# litebrite2_3.net
KiCad netlist of a schematic drawn in EAGLE
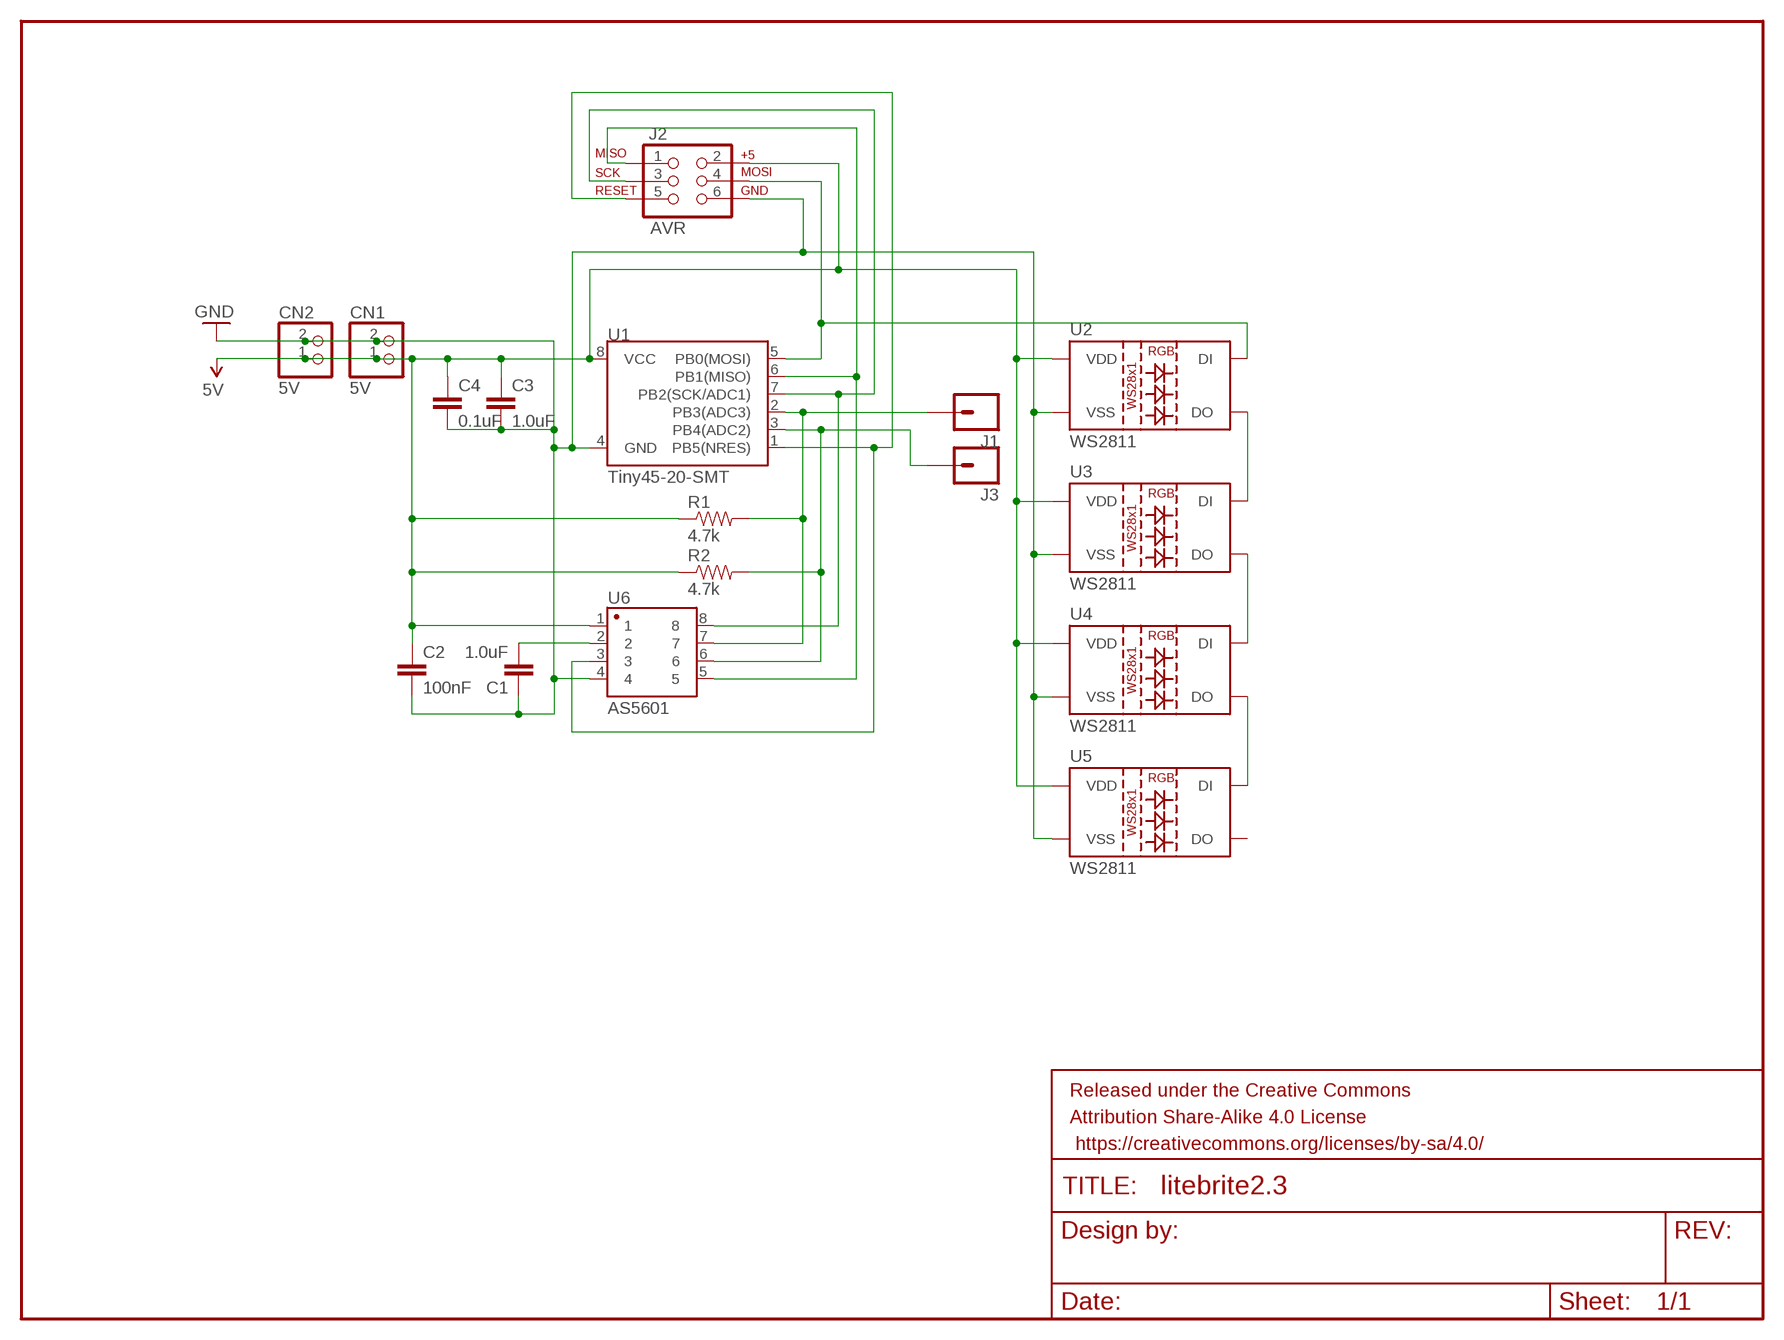
[diagram p0: schematic, sheet 1]

(export (version "E")
  (design (tool "Eeschema 10.0.6"))
  (components
    (comp (ref "C1")
      (value "1.0uF")
      (footprint "eagle-import:0402-CAP")
      (libsource (lib "eagle-import") (part "1.0UF-16V-10%(0402)"))
    )
    (comp (ref "C2")
      (value "100nF")
      (footprint "eagle-import:0402-CAP")
      (libsource (lib "eagle-import") (part "CAP0402-CAP"))
    )
    (comp (ref "C3")
      (value "1.0uF")
      (footprint "eagle-import:0402-CAP")
      (libsource (lib "eagle-import") (part "1.0UF-16V-10%(0402)"))
    )
    (comp (ref "C4")
      (value "0.1uF")
      (footprint "eagle-import:0402-CAP")
      (libsource (lib "eagle-import") (part "0.1UF-16V(+-10%)(0402)"))
    )
    (comp (ref "CN1")
      (value "5V")
      (footprint "eagle-import:JST-PH-2-SMT-RA")
      (libsource (lib "eagle-import") (part "JST_2PIN-SMT-RA"))
    )
    (comp (ref "CN2")
      (value "5V")
      (footprint "eagle-import:JST-PH-2-SMT-RA")
      (libsource (lib "eagle-import") (part "JST_2PIN-SMT-RA"))
    )
    (comp (ref "FRAME1")
      (value "FRAME-LETTERNO_PACKAGE")
      (footprint "eagle-import:DUMMY")
      (fields (field (name "DESIGNER") "Nobody"))
      (libsource (lib "eagle-import") (part "FRAME-LETTERNO_PACKAGE"))
    )
    (comp (ref "J1")
      (value "M01SMD")
      (footprint "eagle-import:LUXEON-PAD")
      (libsource (lib "eagle-import") (part "M01SMD"))
    )
    (comp (ref "J2")
      (value "AVR")
      (footprint "eagle-import:2X3")
      (libsource (lib "eagle-import") (part "AVR_SPI_PRG_6PTH"))
    )
    (comp (ref "J3")
      (value "M01SMD")
      (footprint "eagle-import:LUXEON-PAD")
      (libsource (lib "eagle-import") (part "M01SMD"))
    )
    (comp (ref "R1")
      (value "4.7k")
      (footprint "eagle-import:0603-RES")
      (libsource (lib "eagle-import") (part "4.7OHM-1/10W-5%(0603)"))
    )
    (comp (ref "R2")
      (value "4.7k")
      (footprint "eagle-import:0603-RES")
      (libsource (lib "eagle-import") (part "4.7OHM-1/10W-5%(0603)"))
    )
    (comp (ref "U1")
      (value "Tiny45-20-SMT")
      (footprint "eagle-import:SO08-EIAJ")
      (libsource (lib "eagle-import") (part "ATTINY45TINY45-20-SMT"))
    )
    (comp (ref "U2")
      (value "WS2811")
      (footprint "eagle-import:LED-TRICOLOR-5050-IC")
      (libsource (lib "eagle-import") (part "LED-TRICOLOR-5050-ICWS2811"))
    )
    (comp (ref "U3")
      (value "WS2811")
      (footprint "eagle-import:LED-TRICOLOR-5050-IC")
      (libsource (lib "eagle-import") (part "LED-TRICOLOR-5050-ICWS2811"))
    )
    (comp (ref "U4")
      (value "WS2811")
      (footprint "eagle-import:LED-TRICOLOR-5050-IC")
      (libsource (lib "eagle-import") (part "LED-TRICOLOR-5050-ICWS2811"))
    )
    (comp (ref "U5")
      (value "WS2811")
      (footprint "eagle-import:LED-TRICOLOR-5050-IC")
      (libsource (lib "eagle-import") (part "LED-TRICOLOR-5050-ICWS2811"))
    )
    (comp (ref "U6")
      (value "AS5601")
      (footprint "eagle-import:SO08")
      (libsource (lib "eagle-import") (part "GENERIC-SOIC8MSGEQ7N-FILTER"))
    )
  )
  (nets
    (net (code "1") (name "5V") (class "Default")
      (node (ref "C2") (pin "1") (pinfunction "1_1") (pintype "passive"))
      (node (ref "C3") (pin "1") (pinfunction "1_1") (pintype "passive"))
      (node (ref "C4") (pin "1") (pinfunction "1_1") (pintype "passive"))
      (node (ref "CN1") (pin "1") (pinfunction "2_1") (pintype "passive"))
      (node (ref "CN2") (pin "1") (pinfunction "2_1") (pintype "passive"))
      (node (ref "J2") (pin "2") (pinfunction "2_2") (pintype "passive"))
      (node (ref "R1") (pin "1") (pinfunction "1_1") (pintype "passive"))
      (node (ref "R2") (pin "1") (pinfunction "1_1") (pintype "passive"))
      (node (ref "U1") (pin "8") (pinfunction "VCC_8") (pintype "bidirectional"))
      (node (ref "U2") (pin "3") (pinfunction "VDD_3") (pintype "bidirectional"))
      (node (ref "U2") (pin "5") (pinfunction "VDD_5") (pintype "bidirectional"))
      (node (ref "U3") (pin "3") (pinfunction "VDD_3") (pintype "bidirectional"))
      (node (ref "U3") (pin "5") (pinfunction "VDD_5") (pintype "bidirectional"))
      (node (ref "U4") (pin "3") (pinfunction "VDD_3") (pintype "bidirectional"))
      (node (ref "U4") (pin "5") (pinfunction "VDD_5") (pintype "bidirectional"))
      (node (ref "U5") (pin "3") (pinfunction "VDD_3") (pintype "bidirectional"))
      (node (ref "U5") (pin "5") (pinfunction "VDD_5") (pintype "bidirectional"))
      (node (ref "U6") (pin "1") (pinfunction "1_1") (pintype "bidirectional"))
    )
    (net (code "2") (name "GND") (class "Default")
      (node (ref "C1") (pin "1") (pinfunction "1_1") (pintype "passive"))
      (node (ref "C2") (pin "2") (pinfunction "2_2") (pintype "passive"))
      (node (ref "C3") (pin "2") (pinfunction "2_2") (pintype "passive"))
      (node (ref "C4") (pin "2") (pinfunction "2_2") (pintype "passive"))
      (node (ref "CN1") (pin "2") (pinfunction "1_2") (pintype "passive"))
      (node (ref "CN2") (pin "2") (pinfunction "1_2") (pintype "passive"))
      (node (ref "J2") (pin "6") (pinfunction "6_6") (pintype "passive"))
      (node (ref "U1") (pin "4") (pinfunction "GND_4") (pintype "bidirectional"))
      (node (ref "U2") (pin "6") (pinfunction "VSS_6") (pintype "bidirectional"))
      (node (ref "U3") (pin "6") (pinfunction "VSS_6") (pintype "bidirectional"))
      (node (ref "U4") (pin "6") (pinfunction "VSS_6") (pintype "bidirectional"))
      (node (ref "U5") (pin "6") (pinfunction "VSS_6") (pintype "bidirectional"))
      (node (ref "U6") (pin "4") (pinfunction "4_4") (pintype "bidirectional"))
    )
    (net (code "3") (name "Net-(C1-Pad2)") (class "Default")
      (node (ref "C1") (pin "2") (pinfunction "2_2") (pintype "passive"))
      (node (ref "U6") (pin "2") (pinfunction "2_2") (pintype "bidirectional"))
    )
    (net (code "4") (name "Net-(J1-1)") (class "Default")
      (node (ref "J1") (pin "P$1") (pinfunction "1_P$1") (pintype "passive"))
      (node (ref "R1") (pin "2") (pinfunction "2_2") (pintype "passive"))
      (node (ref "U1") (pin "2") (pinfunction "PB3(ADC3)_2") (pintype "bidirectional"))
      (node (ref "U6") (pin "7") (pinfunction "7_7") (pintype "bidirectional"))
    )
    (net (code "5") (name "Net-(J3-1)") (class "Default")
      (node (ref "J3") (pin "P$1") (pinfunction "1_P$1") (pintype "passive"))
      (node (ref "R2") (pin "2") (pinfunction "2_2") (pintype "passive"))
      (node (ref "U1") (pin "3") (pinfunction "PB4(ADC2)_3") (pintype "bidirectional"))
      (node (ref "U6") (pin "6") (pinfunction "6_6") (pintype "bidirectional"))
    )
    (net (code "6") (name "Net-(U1-PB0(MOSI))") (class "Default")
      (node (ref "J2") (pin "4") (pinfunction "4_4") (pintype "passive"))
      (node (ref "U1") (pin "5") (pinfunction "PB0(MOSI)_5") (pintype "bidirectional"))
      (node (ref "U2") (pin "2") (pinfunction "DI_2") (pintype "bidirectional"))
    )
    (net (code "7") (name "Net-(U1-PB1(MISO))") (class "Default")
      (node (ref "J2") (pin "1") (pinfunction "1_1") (pintype "passive"))
      (node (ref "U1") (pin "6") (pinfunction "PB1(MISO)_6") (pintype "bidirectional"))
      (node (ref "U6") (pin "5") (pinfunction "5_5") (pintype "bidirectional"))
    )
    (net (code "8") (name "Net-(U1-PB2(SCK{slash}ADC1))") (class "Default")
      (node (ref "J2") (pin "3") (pinfunction "3_3") (pintype "passive"))
      (node (ref "U1") (pin "7") (pinfunction "PB2(SCK/ADC1)_7") (pintype "bidirectional"))
      (node (ref "U6") (pin "8") (pinfunction "8_8") (pintype "bidirectional"))
    )
    (net (code "9") (name "Net-(U1-PB5(NRES))") (class "Default")
      (node (ref "J2") (pin "5") (pinfunction "5_5") (pintype "passive"))
      (node (ref "U1") (pin "1") (pinfunction "PB5(NRES)_1") (pintype "bidirectional"))
      (node (ref "U6") (pin "3") (pinfunction "3_3") (pintype "bidirectional"))
    )
    (net (code "10") (name "Net-(U2-DO)") (class "Default")
      (node (ref "U2") (pin "1") (pinfunction "DO_1") (pintype "bidirectional"))
      (node (ref "U3") (pin "2") (pinfunction "DI_2") (pintype "bidirectional"))
    )
    (net (code "11") (name "Net-(U3-DO)") (class "Default")
      (node (ref "U3") (pin "1") (pinfunction "DO_1") (pintype "bidirectional"))
      (node (ref "U4") (pin "2") (pinfunction "DI_2") (pintype "bidirectional"))
    )
    (net (code "12") (name "Net-(U4-DO)") (class "Default")
      (node (ref "U4") (pin "1") (pinfunction "DO_1") (pintype "bidirectional"))
      (node (ref "U5") (pin "2") (pinfunction "DI_2") (pintype "bidirectional"))
    )
    (net (code "13") (name "unconnected-(U5-DO-Pad1)") (class "Default")
      (node (ref "U5") (pin "1") (pinfunction "DO_1") (pintype "bidirectional"))
    )
  )
)
